# Motion_detector_ESP32.net
KiCad netlist of a schematic drawn in Altium Designer
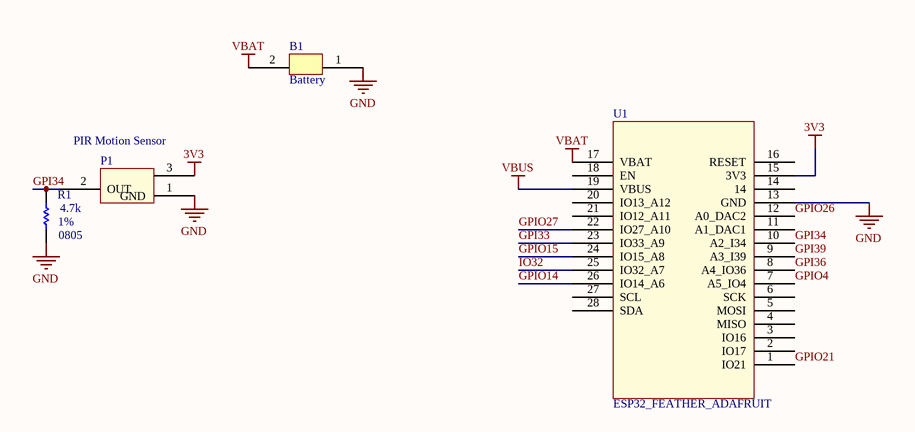
[diagram p0: Motion_detector_ESP32.SchDoc]

(export (version "E")
  (design (tool "Eeschema 10.0.6"))
  (components
    (comp (ref "B1")
      (value "Battery")
      (footprint "battery-3.7V-1200mAh")
      (libsource (lib "S7CAS_Lib2019_REV1_00") (part "Battery"))
    )
    (comp (ref "P1")
      (value "PIR Motion Sensor")
      (footprint "EKMB1301111K")
      (description "Sensor PIR (Passive Infrared) 197\" (5m) 16.4' Polyethylene, White Lens")
      (libsource (lib "S7CAS_Lib2019_REV1_00") (part "PIR Motion Sensor"))
    )
    (comp (ref "R1")
      (value "4.7k")
      (footprint "RES_0805")
      (description "RES - 0805")
      (fields
        (field (name "PACKAGE") "0805")
        (field (name "PRECISION") "1%")
        (field (name "CREATEDBY") "Jonathan Bouchard")
      )
      (libsource (lib "S7CAS_Lib2019_REV1_00") (part "RES - 0805"))
    )
    (comp (ref "U1")
      (value "ESP32_FEATHER_ADAFRUIT")
      (footprint "ESP32_FEATHER")
      (libsource (lib "S7CAS_Lib2019_REV1_00") (part "ESP32_FEATHER_ADAFRUIT"))
    )
  )
  (nets
    (net (code "1") (name "/GPI33") (class "Default")
      (node (ref "U1") (pin "23") (pinfunction "IO33_A9_23") (pintype "passive"))
    )
    (net (code "2") (name "/GPI34") (class "Default")
      (node (ref "P1") (pin "2") (pinfunction "OUT_2") (pintype "passive"))
      (node (ref "R1") (pin "2") (pinfunction "2_2") (pintype "passive"))
      (node (ref "U1") (pin "10") (pinfunction "A2_I34_10") (pintype "passive"))
    )
    (net (code "3") (name "/GPI36") (class "Default")
      (node (ref "U1") (pin "8") (pinfunction "A4_IO36_8") (pintype "passive"))
    )
    (net (code "4") (name "/GPI39") (class "Default")
      (node (ref "U1") (pin "9") (pinfunction "A3_I39_9") (pintype "passive"))
    )
    (net (code "5") (name "/GPIO4") (class "Default")
      (node (ref "U1") (pin "7") (pinfunction "A5_IO4_7") (pintype "passive"))
    )
    (net (code "6") (name "/GPIO14") (class "Default")
      (node (ref "U1") (pin "26") (pinfunction "IO14_A6_26") (pintype "passive"))
    )
    (net (code "7") (name "/GPIO15") (class "Default")
      (node (ref "U1") (pin "24") (pinfunction "IO15_A8_24") (pintype "passive"))
    )
    (net (code "8") (name "/GPIO21") (class "Default")
      (node (ref "U1") (pin "1") (pinfunction "IO21_1") (pintype "passive"))
    )
    (net (code "9") (name "/GPIO26") (class "Default")
      (node (ref "U1") (pin "12") (pinfunction "A0_DAC2_12") (pintype "passive"))
    )
    (net (code "10") (name "/GPIO27") (class "Default")
      (node (ref "U1") (pin "22") (pinfunction "IO27_A10_22") (pintype "passive"))
    )
    (net (code "11") (name "/IO32") (class "Default")
      (node (ref "U1") (pin "25") (pinfunction "IO32_A7_25") (pintype "passive"))
    )
    (net (code "12") (name "3V3") (class "Default")
      (node (ref "P1") (pin "3") (pinfunction "VDD_3") (pintype "passive"))
      (node (ref "U1") (pin "15") (pinfunction "3V3_15") (pintype "passive"))
    )
    (net (code "13") (name "GND") (class "Default")
      (node (ref "B1") (pin "1") (pintype "passive"))
      (node (ref "P1") (pin "1") (pinfunction "GND_1") (pintype "passive"))
      (node (ref "R1") (pin "1") (pinfunction "1_1") (pintype "passive"))
      (node (ref "U1") (pin "13") (pinfunction "GND_13") (pintype "passive"))
    )
    (net (code "14") (name "VBAT") (class "Default")
      (node (ref "B1") (pin "2") (pintype "passive"))
      (node (ref "U1") (pin "17") (pinfunction "VBAT_17") (pintype "passive"))
    )
    (net (code "15") (name "VBUS") (class "Default")
      (node (ref "U1") (pin "19") (pinfunction "VBUS_19") (pintype "passive"))
    )
    (net (code "16") (name "unconnected-(U1-A1_DAC1-Pad11)") (class "Default")
      (node (ref "U1") (pin "11") (pinfunction "A1_DAC1_11") (pintype "passive"))
    )
    (net (code "17") (name "unconnected-(U1-EN-Pad18)") (class "Default")
      (node (ref "U1") (pin "18") (pinfunction "EN_18") (pintype "passive"))
    )
    (net (code "18") (name "unconnected-(U1-IO12_A11-Pad21)") (class "Default")
      (node (ref "U1") (pin "21") (pinfunction "IO12_A11_21") (pintype "passive"))
    )
    (net (code "19") (name "unconnected-(U1-IO13_A12-Pad20)") (class "Default")
      (node (ref "U1") (pin "20") (pinfunction "IO13_A12_20") (pintype "passive"))
    )
    (net (code "20") (name "unconnected-(U1-IO16-Pad3)") (class "Default")
      (node (ref "U1") (pin "3") (pinfunction "IO16_3") (pintype "passive"))
    )
    (net (code "21") (name "unconnected-(U1-IO17-Pad2)") (class "Default")
      (node (ref "U1") (pin "2") (pinfunction "IO17_2") (pintype "passive"))
    )
    (net (code "22") (name "unconnected-(U1-MISO-Pad4)") (class "Default")
      (node (ref "U1") (pin "4") (pinfunction "MISO_4") (pintype "passive"))
    )
    (net (code "23") (name "unconnected-(U1-MOSI-Pad5)") (class "Default")
      (node (ref "U1") (pin "5") (pinfunction "MOSI_5") (pintype "passive"))
    )
    (net (code "24") (name "unconnected-(U1-Pad14)") (class "Default")
      (node (ref "U1") (pin "14") (pinfunction "14_14") (pintype "passive"))
    )
    (net (code "25") (name "unconnected-(U1-RESET-Pad16)") (class "Default")
      (node (ref "U1") (pin "16") (pinfunction "RESET_16") (pintype "passive"))
    )
    (net (code "26") (name "unconnected-(U1-SCK-Pad6)") (class "Default")
      (node (ref "U1") (pin "6") (pinfunction "SCK_6") (pintype "passive"))
    )
    (net (code "27") (name "unconnected-(U1-SCL-Pad27)") (class "Default")
      (node (ref "U1") (pin "27") (pinfunction "SCL_27") (pintype "passive"))
    )
    (net (code "28") (name "unconnected-(U1-SDA-Pad28)") (class "Default")
      (node (ref "U1") (pin "28") (pinfunction "SDA_28") (pintype "passive"))
    )
  )
)
